# SCH_AP4_HWI_diagram.net
KiCad netlist of a schematic drawn in EasyEDA
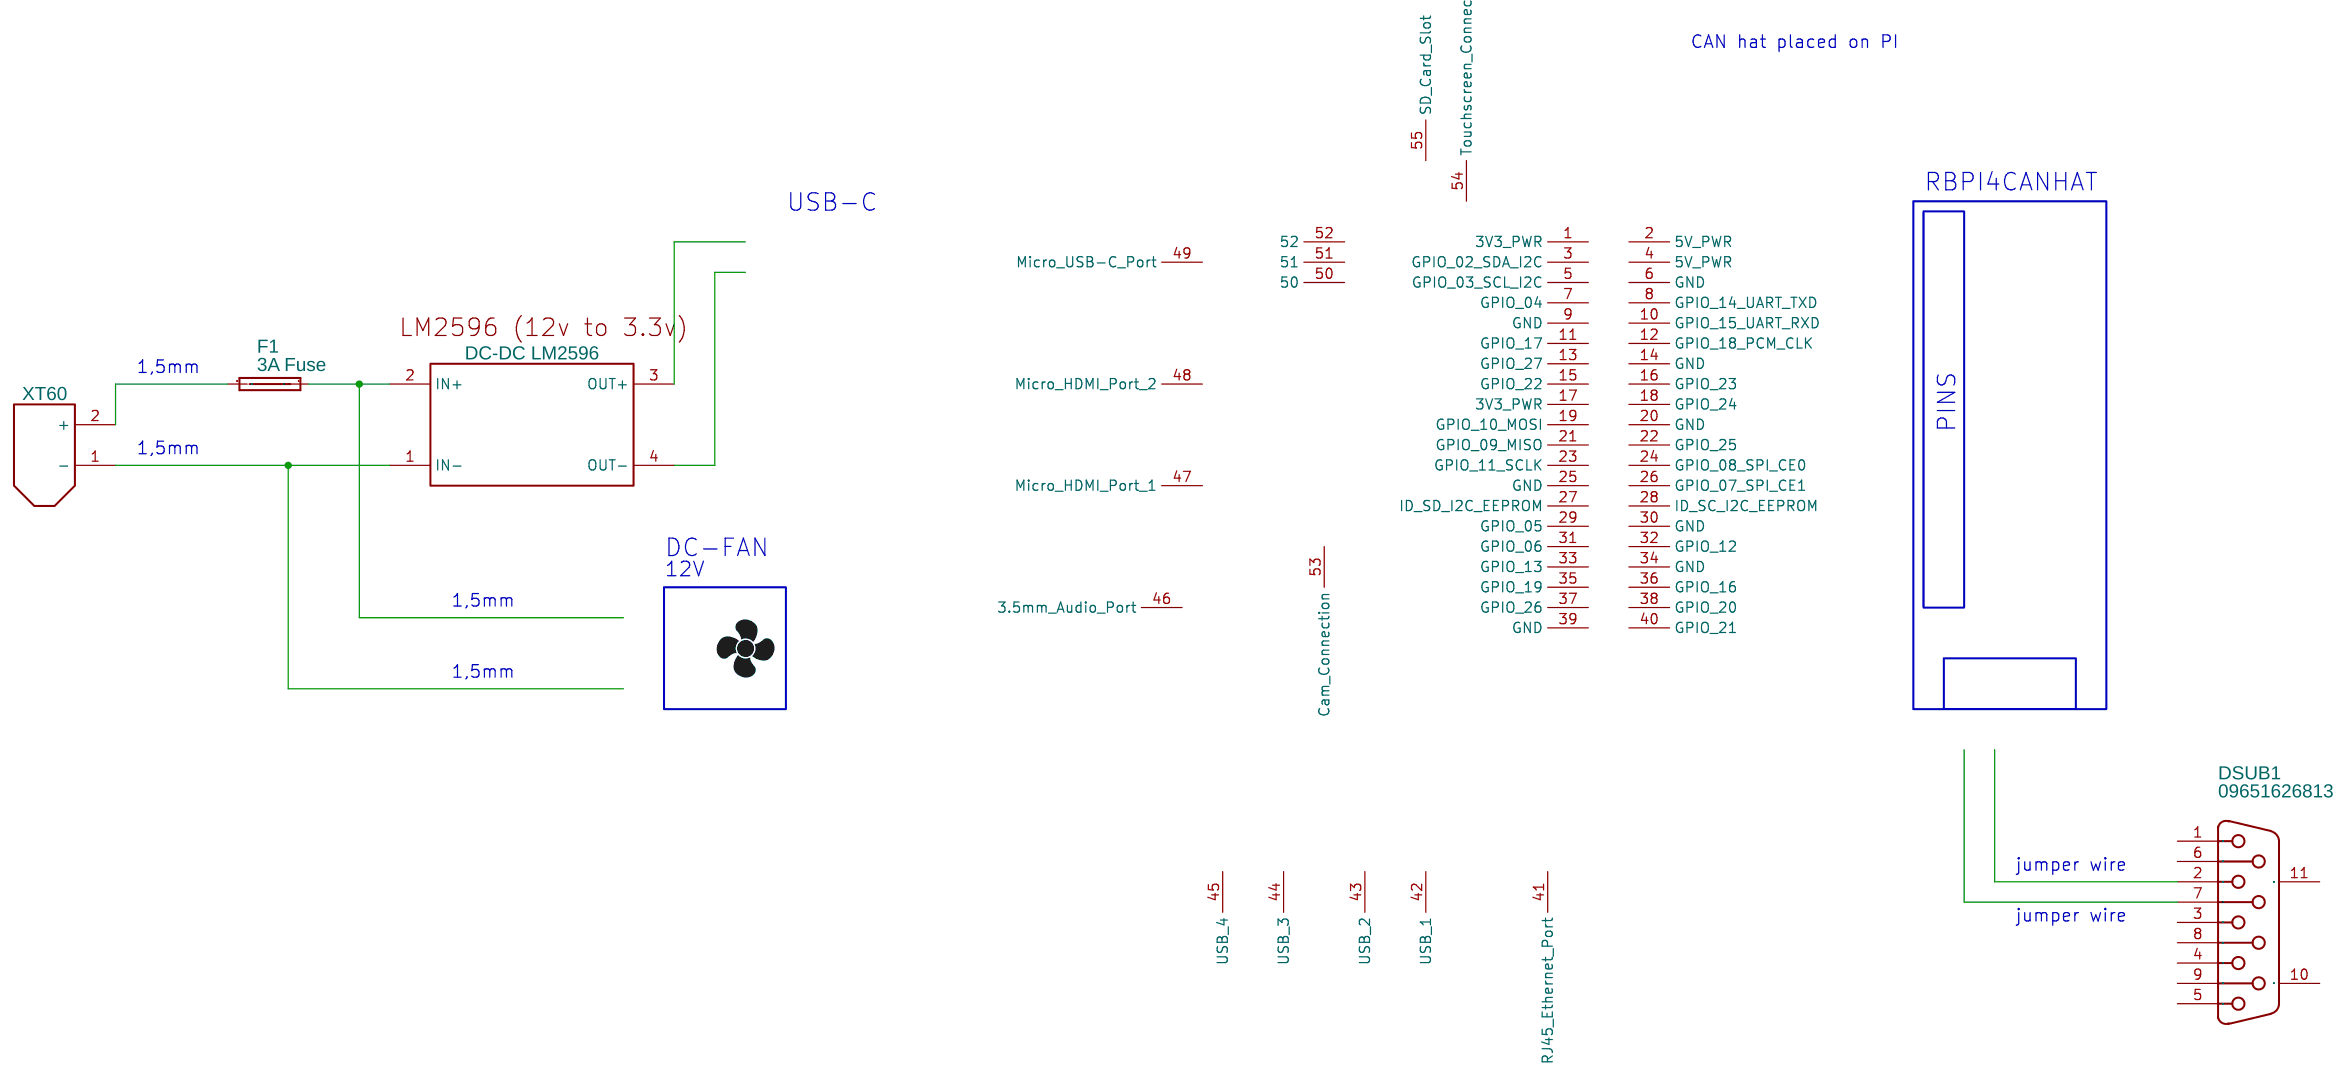
[diagram p0: schematic sheet]

(export (version "E")
  (design (tool "Eeschema 10.0.6"))
  (components
    (comp (ref "B1")
      (value "DC-DC LM2596")
      (fields (field (name "Manufacturer Part") "New SchematicLib"))
      (libsource (lib "") (part "DC-DC LM2596"))
    )
    (comp (ref "DSUB1")
      (value "09651626813")
      (fields (field (name "Manufacturer") "Harting(浩亭)"))
      (libsource (lib "") (part "09651626813"))
    )
    (comp (ref "F1") (value "3A Fuse") (libsource (lib "") (part "FUSE HOLDER WITH COVER FOR 5X20MM FUSE")))
    (comp (ref "NO1")
      (value "XT60")
      (fields (field (name "Manufacturer") "AMASS"))
      (libsource (lib "") (part "XT60"))
    )
    (comp (ref "RASPBERRYPI4") (value "Raspberry Pi 4") (libsource (lib "") (part "Unknown_110_-550")))
  )
  (nets
    (net (code "1") (name "Net-(B1-IN+)") (class "Default")
      (node (ref "B1") (pin "2") (pinfunction "IN+_2") (pintype "unspecified"))
      (node (ref "F1") (pin "1") (pinfunction "1_1") (pintype "unspecified"))
    )
    (net (code "2") (name "Net-(B1-IN-)") (class "Default")
      (node (ref "B1") (pin "1") (pinfunction "IN-_1") (pintype "unspecified"))
      (node (ref "NO1") (pin "1") (pinfunction "-_1") (pintype "unspecified"))
    )
    (net (code "3") (name "Net-(NO1-+)") (class "Default")
      (node (ref "F1") (pin "2") (pinfunction "2_2") (pintype "unspecified"))
      (node (ref "NO1") (pin "2") (pinfunction "+_2") (pintype "unspecified"))
    )
    (net (code "4") (name "unconnected-(B1-OUT+-Pad3)") (class "Default")
      (node (ref "B1") (pin "3") (pinfunction "OUT+_3") (pintype "unspecified"))
    )
    (net (code "5") (name "unconnected-(B1-OUT--Pad4)") (class "Default")
      (node (ref "B1") (pin "4") (pinfunction "OUT-_4") (pintype "unspecified"))
    )
    (net (code "6") (name "unconnected-(DSUB1-MH1-Pad10)") (class "Default")
      (node (ref "DSUB1") (pin "10") (pinfunction "MH1_10") (pintype "input"))
    )
    (net (code "7") (name "unconnected-(DSUB1-MH2-Pad11)") (class "Default")
      (node (ref "DSUB1") (pin "11") (pinfunction "MH2_11") (pintype "input"))
    )
    (net (code "8") (name "unconnected-(DSUB1-Pad1)") (class "Default")
      (node (ref "DSUB1") (pin "1") (pinfunction "1_1") (pintype "input"))
    )
    (net (code "9") (name "unconnected-(DSUB1-Pad2)") (class "Default")
      (node (ref "DSUB1") (pin "2") (pinfunction "2_2") (pintype "input"))
    )
    (net (code "10") (name "unconnected-(DSUB1-Pad3)") (class "Default")
      (node (ref "DSUB1") (pin "3") (pinfunction "3_3") (pintype "input"))
    )
    (net (code "11") (name "unconnected-(DSUB1-Pad4)") (class "Default")
      (node (ref "DSUB1") (pin "4") (pinfunction "4_4") (pintype "input"))
    )
    (net (code "12") (name "unconnected-(DSUB1-Pad5)") (class "Default")
      (node (ref "DSUB1") (pin "5") (pinfunction "5_5") (pintype "input"))
    )
    (net (code "13") (name "unconnected-(DSUB1-Pad6)") (class "Default")
      (node (ref "DSUB1") (pin "6") (pinfunction "6_6") (pintype "input"))
    )
    (net (code "14") (name "unconnected-(DSUB1-Pad7)") (class "Default")
      (node (ref "DSUB1") (pin "7") (pinfunction "7_7") (pintype "input"))
    )
    (net (code "15") (name "unconnected-(DSUB1-Pad8)") (class "Default")
      (node (ref "DSUB1") (pin "8") (pinfunction "8_8") (pintype "input"))
    )
    (net (code "16") (name "unconnected-(DSUB1-Pad9)") (class "Default")
      (node (ref "DSUB1") (pin "9") (pinfunction "9_9") (pintype "input"))
    )
    (net (code "17") (name "unconnected-(RASPBERRYPI4-3.5mm_Audio_Port-Pad46)") (class "Default")
      (node (ref "RASPBERRYPI4") (pin "46") (pinfunction "3.5mm_Audio_Port_46") (pintype "unspecified"))
    )
    (net (code "18") (name "unconnected-(RASPBERRYPI4-3V3_PWR-Pad1)") (class "Default")
      (node (ref "RASPBERRYPI4") (pin "1") (pinfunction "3V3_PWR_1") (pintype "unspecified"))
    )
    (net (code "19") (name "unconnected-(RASPBERRYPI4-3V3_PWR-Pad17)") (class "Default")
      (node (ref "RASPBERRYPI4") (pin "17") (pinfunction "3V3_PWR_17") (pintype "unspecified"))
    )
    (net (code "20") (name "unconnected-(RASPBERRYPI4-5V_PWR-Pad2)") (class "Default")
      (node (ref "RASPBERRYPI4") (pin "2") (pinfunction "5V_PWR_2") (pintype "unspecified"))
    )
    (net (code "21") (name "unconnected-(RASPBERRYPI4-5V_PWR-Pad4)") (class "Default")
      (node (ref "RASPBERRYPI4") (pin "4") (pinfunction "5V_PWR_4") (pintype "unspecified"))
    )
    (net (code "22") (name "unconnected-(RASPBERRYPI4-Cam_Connection-Pad53)") (class "Default")
      (node (ref "RASPBERRYPI4") (pin "53") (pinfunction "Cam_Connection_53") (pintype "unspecified"))
    )
    (net (code "23") (name "unconnected-(RASPBERRYPI4-GND-Pad6)") (class "Default")
      (node (ref "RASPBERRYPI4") (pin "6") (pinfunction "GND_6") (pintype "unspecified"))
    )
    (net (code "24") (name "unconnected-(RASPBERRYPI4-GND-Pad9)") (class "Default")
      (node (ref "RASPBERRYPI4") (pin "9") (pinfunction "GND_9") (pintype "unspecified"))
    )
    (net (code "25") (name "unconnected-(RASPBERRYPI4-GND-Pad14)") (class "Default")
      (node (ref "RASPBERRYPI4") (pin "14") (pinfunction "GND_14") (pintype "unspecified"))
    )
    (net (code "26") (name "unconnected-(RASPBERRYPI4-GND-Pad20)") (class "Default")
      (node (ref "RASPBERRYPI4") (pin "20") (pinfunction "GND_20") (pintype "unspecified"))
    )
    (net (code "27") (name "unconnected-(RASPBERRYPI4-GND-Pad25)") (class "Default")
      (node (ref "RASPBERRYPI4") (pin "25") (pinfunction "GND_25") (pintype "unspecified"))
    )
    (net (code "28") (name "unconnected-(RASPBERRYPI4-GND-Pad30)") (class "Default")
      (node (ref "RASPBERRYPI4") (pin "30") (pinfunction "GND_30") (pintype "unspecified"))
    )
    (net (code "29") (name "unconnected-(RASPBERRYPI4-GND-Pad34)") (class "Default")
      (node (ref "RASPBERRYPI4") (pin "34") (pinfunction "GND_34") (pintype "unspecified"))
    )
    (net (code "30") (name "unconnected-(RASPBERRYPI4-GND-Pad39)") (class "Default")
      (node (ref "RASPBERRYPI4") (pin "39") (pinfunction "GND_39") (pintype "unspecified"))
    )
    (net (code "31") (name "unconnected-(RASPBERRYPI4-GPIO_02_SDA_I2C-Pad3)") (class "Default")
      (node (ref "RASPBERRYPI4") (pin "3") (pinfunction "GPIO_02_SDA_I2C_3") (pintype "unspecified"))
    )
    (net (code "32") (name "unconnected-(RASPBERRYPI4-GPIO_03_SCL_I2C-Pad5)") (class "Default")
      (node (ref "RASPBERRYPI4") (pin "5") (pinfunction "GPIO_03_SCL_I2C_5") (pintype "unspecified"))
    )
    (net (code "33") (name "unconnected-(RASPBERRYPI4-GPIO_04-Pad7)") (class "Default")
      (node (ref "RASPBERRYPI4") (pin "7") (pinfunction "GPIO_04_7") (pintype "unspecified"))
    )
    (net (code "34") (name "unconnected-(RASPBERRYPI4-GPIO_05-Pad29)") (class "Default")
      (node (ref "RASPBERRYPI4") (pin "29") (pinfunction "GPIO_05_29") (pintype "unspecified"))
    )
    (net (code "35") (name "unconnected-(RASPBERRYPI4-GPIO_06-Pad31)") (class "Default")
      (node (ref "RASPBERRYPI4") (pin "31") (pinfunction "GPIO_06_31") (pintype "unspecified"))
    )
    (net (code "36") (name "unconnected-(RASPBERRYPI4-GPIO_07_SPI_CE1-Pad26)") (class "Default")
      (node (ref "RASPBERRYPI4") (pin "26") (pinfunction "GPIO_07_SPI_CE1_26") (pintype "unspecified"))
    )
    (net (code "37") (name "unconnected-(RASPBERRYPI4-GPIO_08_SPI_CE0-Pad24)") (class "Default")
      (node (ref "RASPBERRYPI4") (pin "24") (pinfunction "GPIO_08_SPI_CE0_24") (pintype "unspecified"))
    )
    (net (code "38") (name "unconnected-(RASPBERRYPI4-GPIO_09_MISO-Pad21)") (class "Default")
      (node (ref "RASPBERRYPI4") (pin "21") (pinfunction "GPIO_09_MISO_21") (pintype "unspecified"))
    )
    (net (code "39") (name "unconnected-(RASPBERRYPI4-GPIO_10_MOSI-Pad19)") (class "Default")
      (node (ref "RASPBERRYPI4") (pin "19") (pinfunction "GPIO_10_MOSI_19") (pintype "unspecified"))
    )
    (net (code "40") (name "unconnected-(RASPBERRYPI4-GPIO_11_SCLK-Pad23)") (class "Default")
      (node (ref "RASPBERRYPI4") (pin "23") (pinfunction "GPIO_11_SCLK_23") (pintype "unspecified"))
    )
    (net (code "41") (name "unconnected-(RASPBERRYPI4-GPIO_12-Pad32)") (class "Default")
      (node (ref "RASPBERRYPI4") (pin "32") (pinfunction "GPIO_12_32") (pintype "unspecified"))
    )
    (net (code "42") (name "unconnected-(RASPBERRYPI4-GPIO_13-Pad33)") (class "Default")
      (node (ref "RASPBERRYPI4") (pin "33") (pinfunction "GPIO_13_33") (pintype "unspecified"))
    )
    (net (code "43") (name "unconnected-(RASPBERRYPI4-GPIO_14_UART_TXD-Pad8)") (class "Default")
      (node (ref "RASPBERRYPI4") (pin "8") (pinfunction "GPIO_14_UART_TXD_8") (pintype "unspecified"))
    )
    (net (code "44") (name "unconnected-(RASPBERRYPI4-GPIO_15_UART_RXD-Pad10)") (class "Default")
      (node (ref "RASPBERRYPI4") (pin "10") (pinfunction "GPIO_15_UART_RXD_10") (pintype "unspecified"))
    )
    (net (code "45") (name "unconnected-(RASPBERRYPI4-GPIO_16-Pad36)") (class "Default")
      (node (ref "RASPBERRYPI4") (pin "36") (pinfunction "GPIO_16_36") (pintype "unspecified"))
    )
    (net (code "46") (name "unconnected-(RASPBERRYPI4-GPIO_17-Pad11)") (class "Default")
      (node (ref "RASPBERRYPI4") (pin "11") (pinfunction "GPIO_17_11") (pintype "unspecified"))
    )
    (net (code "47") (name "unconnected-(RASPBERRYPI4-GPIO_18_PCM_CLK-Pad12)") (class "Default")
      (node (ref "RASPBERRYPI4") (pin "12") (pinfunction "GPIO_18_PCM_CLK_12") (pintype "unspecified"))
    )
    (net (code "48") (name "unconnected-(RASPBERRYPI4-GPIO_19-Pad35)") (class "Default")
      (node (ref "RASPBERRYPI4") (pin "35") (pinfunction "GPIO_19_35") (pintype "unspecified"))
    )
    (net (code "49") (name "unconnected-(RASPBERRYPI4-GPIO_20-Pad38)") (class "Default")
      (node (ref "RASPBERRYPI4") (pin "38") (pinfunction "GPIO_20_38") (pintype "unspecified"))
    )
    (net (code "50") (name "unconnected-(RASPBERRYPI4-GPIO_21-Pad40)") (class "Default")
      (node (ref "RASPBERRYPI4") (pin "40") (pinfunction "GPIO_21_40") (pintype "unspecified"))
    )
    (net (code "51") (name "unconnected-(RASPBERRYPI4-GPIO_22-Pad15)") (class "Default")
      (node (ref "RASPBERRYPI4") (pin "15") (pinfunction "GPIO_22_15") (pintype "unspecified"))
    )
    (net (code "52") (name "unconnected-(RASPBERRYPI4-GPIO_23-Pad16)") (class "Default")
      (node (ref "RASPBERRYPI4") (pin "16") (pinfunction "GPIO_23_16") (pintype "unspecified"))
    )
    (net (code "53") (name "unconnected-(RASPBERRYPI4-GPIO_24-Pad18)") (class "Default")
      (node (ref "RASPBERRYPI4") (pin "18") (pinfunction "GPIO_24_18") (pintype "unspecified"))
    )
    (net (code "54") (name "unconnected-(RASPBERRYPI4-GPIO_25-Pad22)") (class "Default")
      (node (ref "RASPBERRYPI4") (pin "22") (pinfunction "GPIO_25_22") (pintype "unspecified"))
    )
    (net (code "55") (name "unconnected-(RASPBERRYPI4-GPIO_26-Pad37)") (class "Default")
      (node (ref "RASPBERRYPI4") (pin "37") (pinfunction "GPIO_26_37") (pintype "unspecified"))
    )
    (net (code "56") (name "unconnected-(RASPBERRYPI4-GPIO_27-Pad13)") (class "Default")
      (node (ref "RASPBERRYPI4") (pin "13") (pinfunction "GPIO_27_13") (pintype "unspecified"))
    )
    (net (code "57") (name "unconnected-(RASPBERRYPI4-ID_SC_I2C_EEPROM-Pad28)") (class "Default")
      (node (ref "RASPBERRYPI4") (pin "28") (pinfunction "ID_SC_I2C_EEPROM_28") (pintype "unspecified"))
    )
    (net (code "58") (name "unconnected-(RASPBERRYPI4-ID_SD_I2C_EEPROM-Pad27)") (class "Default")
      (node (ref "RASPBERRYPI4") (pin "27") (pinfunction "ID_SD_I2C_EEPROM_27") (pintype "unspecified"))
    )
    (net (code "59") (name "unconnected-(RASPBERRYPI4-Micro_HDMI_Port_1-Pad47)") (class "Default")
      (node (ref "RASPBERRYPI4") (pin "47") (pinfunction "Micro_HDMI_Port_1_47") (pintype "unspecified"))
    )
    (net (code "60") (name "unconnected-(RASPBERRYPI4-Micro_HDMI_Port_2-Pad48)") (class "Default")
      (node (ref "RASPBERRYPI4") (pin "48") (pinfunction "Micro_HDMI_Port_2_48") (pintype "unspecified"))
    )
    (net (code "61") (name "unconnected-(RASPBERRYPI4-Micro_USB-C_Port-Pad49)") (class "Default")
      (node (ref "RASPBERRYPI4") (pin "49") (pinfunction "Micro_USB-C_Port_49") (pintype "unspecified"))
    )
    (net (code "62") (name "unconnected-(RASPBERRYPI4-Pad50)") (class "Default")
      (node (ref "RASPBERRYPI4") (pin "50") (pinfunction "50_50") (pintype "unspecified"))
    )
    (net (code "63") (name "unconnected-(RASPBERRYPI4-Pad51)") (class "Default")
      (node (ref "RASPBERRYPI4") (pin "51") (pinfunction "51_51") (pintype "unspecified"))
    )
    (net (code "64") (name "unconnected-(RASPBERRYPI4-Pad52)") (class "Default")
      (node (ref "RASPBERRYPI4") (pin "52") (pinfunction "52_52") (pintype "unspecified"))
    )
    (net (code "65") (name "unconnected-(RASPBERRYPI4-RJ45_Ethernet_Port-Pad41)") (class "Default")
      (node (ref "RASPBERRYPI4") (pin "41") (pinfunction "RJ45_Ethernet_Port_41") (pintype "unspecified"))
    )
    (net (code "66") (name "unconnected-(RASPBERRYPI4-SD_Card_Slot-Pad55)") (class "Default")
      (node (ref "RASPBERRYPI4") (pin "55") (pinfunction "SD_Card_Slot_55") (pintype "unspecified"))
    )
    (net (code "67") (name "unconnected-(RASPBERRYPI4-Touchscreen_Connection-Pad54)") (class "Default")
      (node (ref "RASPBERRYPI4") (pin "54") (pinfunction "Touchscreen_Connection_54") (pintype "unspecified"))
    )
    (net (code "68") (name "unconnected-(RASPBERRYPI4-USB_1-Pad42)") (class "Default")
      (node (ref "RASPBERRYPI4") (pin "42") (pinfunction "USB_1_42") (pintype "unspecified"))
    )
    (net (code "69") (name "unconnected-(RASPBERRYPI4-USB_2-Pad43)") (class "Default")
      (node (ref "RASPBERRYPI4") (pin "43") (pinfunction "USB_2_43") (pintype "unspecified"))
    )
    (net (code "70") (name "unconnected-(RASPBERRYPI4-USB_3-Pad44)") (class "Default")
      (node (ref "RASPBERRYPI4") (pin "44") (pinfunction "USB_3_44") (pintype "unspecified"))
    )
    (net (code "71") (name "unconnected-(RASPBERRYPI4-USB_4-Pad45)") (class "Default")
      (node (ref "RASPBERRYPI4") (pin "45") (pinfunction "USB_4_45") (pintype "unspecified"))
    )
  )
)
